# ESP-WROOM-32.net
KiCad netlist of a schematic drawn in Altium Designer
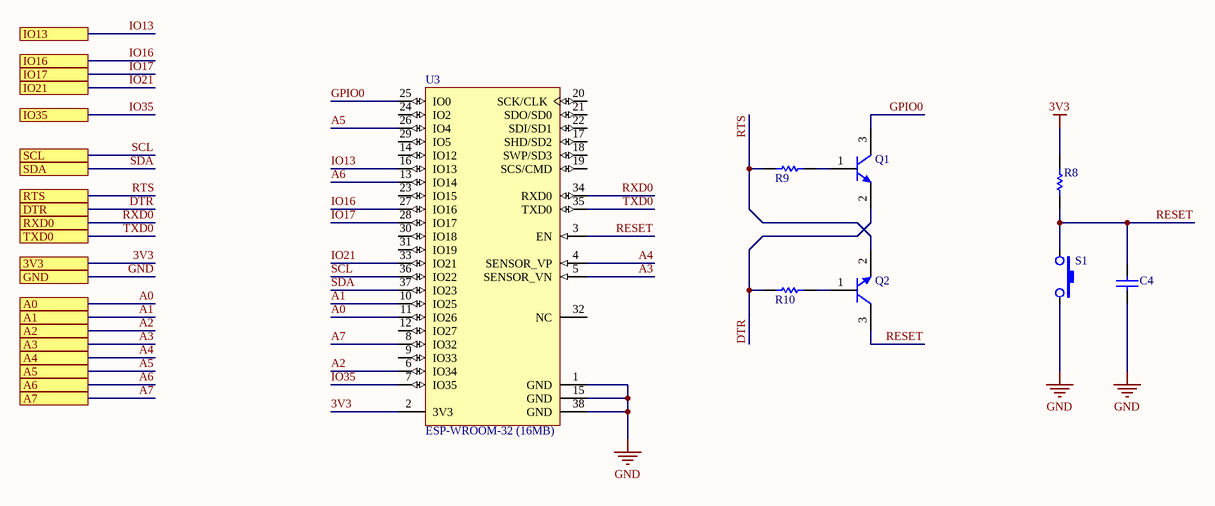
[diagram p0: ESP-WROOM-32.SchDoc]

(export (version "E")
  (design (tool "Eeschema 10.0.6"))
  (components
    (comp (ref "C4")
      (value "C0805C105K4RAC7800")
      (footprint "CAPC2013X145X50NL20T25")
      (description "1µF ±10% 16V Ceramic Capacitor X7R 0805 (2012 Metric)")
      (fields (field (name "MANUFACTURER") "Kemet"))
      (libsource (lib "Altium Content Vault") (part "CAP"))
    )
    (comp (ref "Q1")
      (value "MMBT2222ALT1G")
      (footprint "ONSC-SOT-23-3-318-08_V")
      (description "General Purpose Transistor, NPN Silicon, 3-Pin SOT-23, Pb-Free, Tape and Reel")
      (fields (field (name "MANUFACTURER") "On Semiconductor"))
      (libsource (lib "Altium Content Vault") (part "ONSC-NPN-B1E2C3-3"))
    )
    (comp (ref "Q2")
      (value "MMBT2222ALT1G")
      (footprint "ONSC-SOT-23-3-318-08_V")
      (description "General Purpose Transistor, NPN Silicon, 3-Pin SOT-23, Pb-Free, Tape and Reel")
      (fields (field (name "MANUFACTURER") "On Semiconductor"))
      (libsource (lib "Altium Content Vault") (part "ONSC-NPN-B1E2C3-3"))
    )
    (comp (ref "R8")
      (value "RK73B2ATTD103J")
      (footprint "RESC2013X60X30NL20T20")
      (fields (field (name "MANUFACTURER") "KOA Speer"))
      (libsource (lib "Altium Content Vault") (part "RES"))
    )
    (comp (ref "R9")
      (value "RK73B2ATTD103J")
      (footprint "RESC2013X60X30NL20T20")
      (fields (field (name "MANUFACTURER") "KOA Speer"))
      (libsource (lib "Altium Content Vault") (part "RES"))
    )
    (comp (ref "R10")
      (value "RK73B2ATTD103J")
      (footprint "RESC2013X60X30NL20T20")
      (fields (field (name "MANUFACTURER") "KOA Speer"))
      (libsource (lib "Altium Content Vault") (part "RES"))
    )
    (comp (ref "S1")
      (value "PTS820J25MSMTRLFS")
      (footprint "SMT_SW_PTS_820")
      (description "Tactile Switch SPST-NO Top Actuated Surface Moun")
      (libsource (lib "LIB_FIT") (part "PTS820J25MSMTRLFS"))
    )
    (comp (ref "U3")
      (value "ESP-WROOM-32 (16MB)")
      (footprint "OLMX-ESP-WROOM-32")
      (description "Espressif System, 2.7 to 3.6 V, -40 to 85 degC, 38-Pin SMD")
      (libsource (lib "Altium Content Vault") (part "OLMX-ESP-WROOM-32-38"))
    )
  )
  (nets
    (net (code "1") (name "/A0") (class "Default")
      (node (ref "U3") (pin "11") (pinfunction "IO26_11") (pintype "bidirectional"))
    )
    (net (code "2") (name "/A1") (class "Default")
      (node (ref "U3") (pin "10") (pinfunction "IO25_10") (pintype "bidirectional"))
    )
    (net (code "3") (name "/A2") (class "Default")
      (node (ref "U3") (pin "6") (pinfunction "IO34_6") (pintype "bidirectional"))
    )
    (net (code "4") (name "/A3") (class "Default")
      (node (ref "U3") (pin "5") (pinfunction "SENSOR_VN_5") (pintype "input"))
    )
    (net (code "5") (name "/A4") (class "Default")
      (node (ref "U3") (pin "4") (pinfunction "SENSOR_VP_4") (pintype "input"))
    )
    (net (code "6") (name "/A5") (class "Default")
      (node (ref "U3") (pin "26") (pinfunction "IO4_26") (pintype "bidirectional"))
    )
    (net (code "7") (name "/A6") (class "Default")
      (node (ref "U3") (pin "13") (pinfunction "IO14_13") (pintype "bidirectional"))
    )
    (net (code "8") (name "/A7") (class "Default")
      (node (ref "U3") (pin "8") (pinfunction "IO32_8") (pintype "bidirectional"))
    )
    (net (code "9") (name "/DTR") (class "Default")
      (node (ref "Q1") (pin "2") (pinfunction "E_2") (pintype "passive"))
      (node (ref "R10") (pin "2") (pinfunction "2_2") (pintype "passive"))
    )
    (net (code "10") (name "/GPIO0") (class "Default")
      (node (ref "Q1") (pin "3") (pinfunction "C_3") (pintype "passive"))
      (node (ref "U3") (pin "25") (pinfunction "IO0_25") (pintype "bidirectional"))
    )
    (net (code "11") (name "/IO13") (class "Default")
      (node (ref "U3") (pin "16") (pinfunction "IO13_16") (pintype "bidirectional"))
    )
    (net (code "12") (name "/IO16") (class "Default")
      (node (ref "U3") (pin "27") (pinfunction "IO16_27") (pintype "bidirectional"))
    )
    (net (code "13") (name "/IO17") (class "Default")
      (node (ref "U3") (pin "28") (pinfunction "IO17_28") (pintype "bidirectional"))
    )
    (net (code "14") (name "/IO21") (class "Default")
      (node (ref "U3") (pin "33") (pinfunction "IO21_33") (pintype "bidirectional"))
    )
    (net (code "15") (name "/IO35") (class "Default")
      (node (ref "U3") (pin "7") (pinfunction "IO35_7") (pintype "bidirectional"))
    )
    (net (code "16") (name "/RESET") (class "Default")
      (node (ref "C4") (pin "2") (pinfunction "2_2") (pintype "passive"))
      (node (ref "Q2") (pin "3") (pinfunction "C_3") (pintype "passive"))
      (node (ref "R8") (pin "1") (pinfunction "1_1") (pintype "passive"))
      (node (ref "S1") (pin "1") (pinfunction "1_1") (pintype "passive"))
      (node (ref "U3") (pin "3") (pinfunction "EN_3") (pintype "input"))
    )
    (net (code "17") (name "/RTS") (class "Default")
      (node (ref "Q2") (pin "2") (pinfunction "E_2") (pintype "passive"))
      (node (ref "R9") (pin "2") (pinfunction "2_2") (pintype "passive"))
    )
    (net (code "18") (name "/RXD0") (class "Default")
      (node (ref "U3") (pin "34") (pinfunction "RXD0_34") (pintype "bidirectional"))
    )
    (net (code "19") (name "/SCL") (class "Default")
      (node (ref "U3") (pin "36") (pinfunction "IO22_36") (pintype "bidirectional"))
    )
    (net (code "20") (name "/SDA") (class "Default")
      (node (ref "U3") (pin "37") (pinfunction "IO23_37") (pintype "bidirectional"))
    )
    (net (code "21") (name "/TXD0") (class "Default")
      (node (ref "U3") (pin "35") (pinfunction "TXD0_35") (pintype "bidirectional"))
    )
    (net (code "22") (name "3V3") (class "Default")
      (node (ref "R8") (pin "2") (pinfunction "2_2") (pintype "passive"))
      (node (ref "U3") (pin "2") (pinfunction "3V3_2") (pintype "power_in"))
    )
    (net (code "23") (name "GND") (class "Default")
      (node (ref "C4") (pin "1") (pinfunction "1_1") (pintype "passive"))
      (node (ref "S1") (pin "2") (pinfunction "2_2") (pintype "passive"))
      (node (ref "U3") (pin "1") (pinfunction "GND_1") (pintype "power_in"))
      (node (ref "U3") (pin "15") (pinfunction "GND_15") (pintype "power_in"))
      (node (ref "U3") (pin "38") (pinfunction "GND_38") (pintype "power_in"))
    )
    (net (code "24") (name "Net-(Q1-B)") (class "Default")
      (node (ref "Q1") (pin "1") (pinfunction "B_1") (pintype "passive"))
      (node (ref "R9") (pin "1") (pinfunction "1_1") (pintype "passive"))
    )
    (net (code "25") (name "Net-(Q2-B)") (class "Default")
      (node (ref "Q2") (pin "1") (pinfunction "B_1") (pintype "passive"))
      (node (ref "R10") (pin "1") (pinfunction "1_1") (pintype "passive"))
    )
    (net (code "26") (name "unconnected-(U3-IO2-Pad24)") (class "Default")
      (node (ref "U3") (pin "24") (pinfunction "IO2_24") (pintype "bidirectional"))
    )
    (net (code "27") (name "unconnected-(U3-IO5-Pad29)") (class "Default")
      (node (ref "U3") (pin "29") (pinfunction "IO5_29") (pintype "bidirectional"))
    )
    (net (code "28") (name "unconnected-(U3-IO12-Pad14)") (class "Default")
      (node (ref "U3") (pin "14") (pinfunction "IO12_14") (pintype "bidirectional"))
    )
    (net (code "29") (name "unconnected-(U3-IO15-Pad23)") (class "Default")
      (node (ref "U3") (pin "23") (pinfunction "IO15_23") (pintype "bidirectional"))
    )
    (net (code "30") (name "unconnected-(U3-IO18-Pad30)") (class "Default")
      (node (ref "U3") (pin "30") (pinfunction "IO18_30") (pintype "bidirectional"))
    )
    (net (code "31") (name "unconnected-(U3-IO19-Pad31)") (class "Default")
      (node (ref "U3") (pin "31") (pinfunction "IO19_31") (pintype "bidirectional"))
    )
    (net (code "32") (name "unconnected-(U3-IO27-Pad12)") (class "Default")
      (node (ref "U3") (pin "12") (pinfunction "IO27_12") (pintype "bidirectional"))
    )
    (net (code "33") (name "unconnected-(U3-IO33-Pad9)") (class "Default")
      (node (ref "U3") (pin "9") (pinfunction "IO33_9") (pintype "bidirectional"))
    )
    (net (code "34") (name "unconnected-(U3-NC-Pad32)") (class "Default")
      (node (ref "U3") (pin "32") (pinfunction "NC_32") (pintype "passive"))
    )
    (net (code "35") (name "unconnected-(U3-SCK{slash}CLK-Pad20)") (class "Default")
      (node (ref "U3") (pin "20") (pinfunction "SCK/CLK_20") (pintype "bidirectional"))
    )
    (net (code "36") (name "unconnected-(U3-SCS{slash}CMD-Pad19)") (class "Default")
      (node (ref "U3") (pin "19") (pinfunction "SCS/CMD_19") (pintype "bidirectional"))
    )
    (net (code "37") (name "unconnected-(U3-SDI{slash}SD1-Pad22)") (class "Default")
      (node (ref "U3") (pin "22") (pinfunction "SDI/SD1_22") (pintype "bidirectional"))
    )
    (net (code "38") (name "unconnected-(U3-SDO{slash}SD0-Pad21)") (class "Default")
      (node (ref "U3") (pin "21") (pinfunction "SDO/SD0_21") (pintype "bidirectional"))
    )
    (net (code "39") (name "unconnected-(U3-SHD{slash}SD2-Pad17)") (class "Default")
      (node (ref "U3") (pin "17") (pinfunction "SHD/SD2_17") (pintype "bidirectional"))
    )
    (net (code "40") (name "unconnected-(U3-SWP{slash}SD3-Pad18)") (class "Default")
      (node (ref "U3") (pin "18") (pinfunction "SWP/SD3_18") (pintype "bidirectional"))
    )
  )
)
